# PCB.net
KiCad netlist of a schematic drawn in Altium Designer
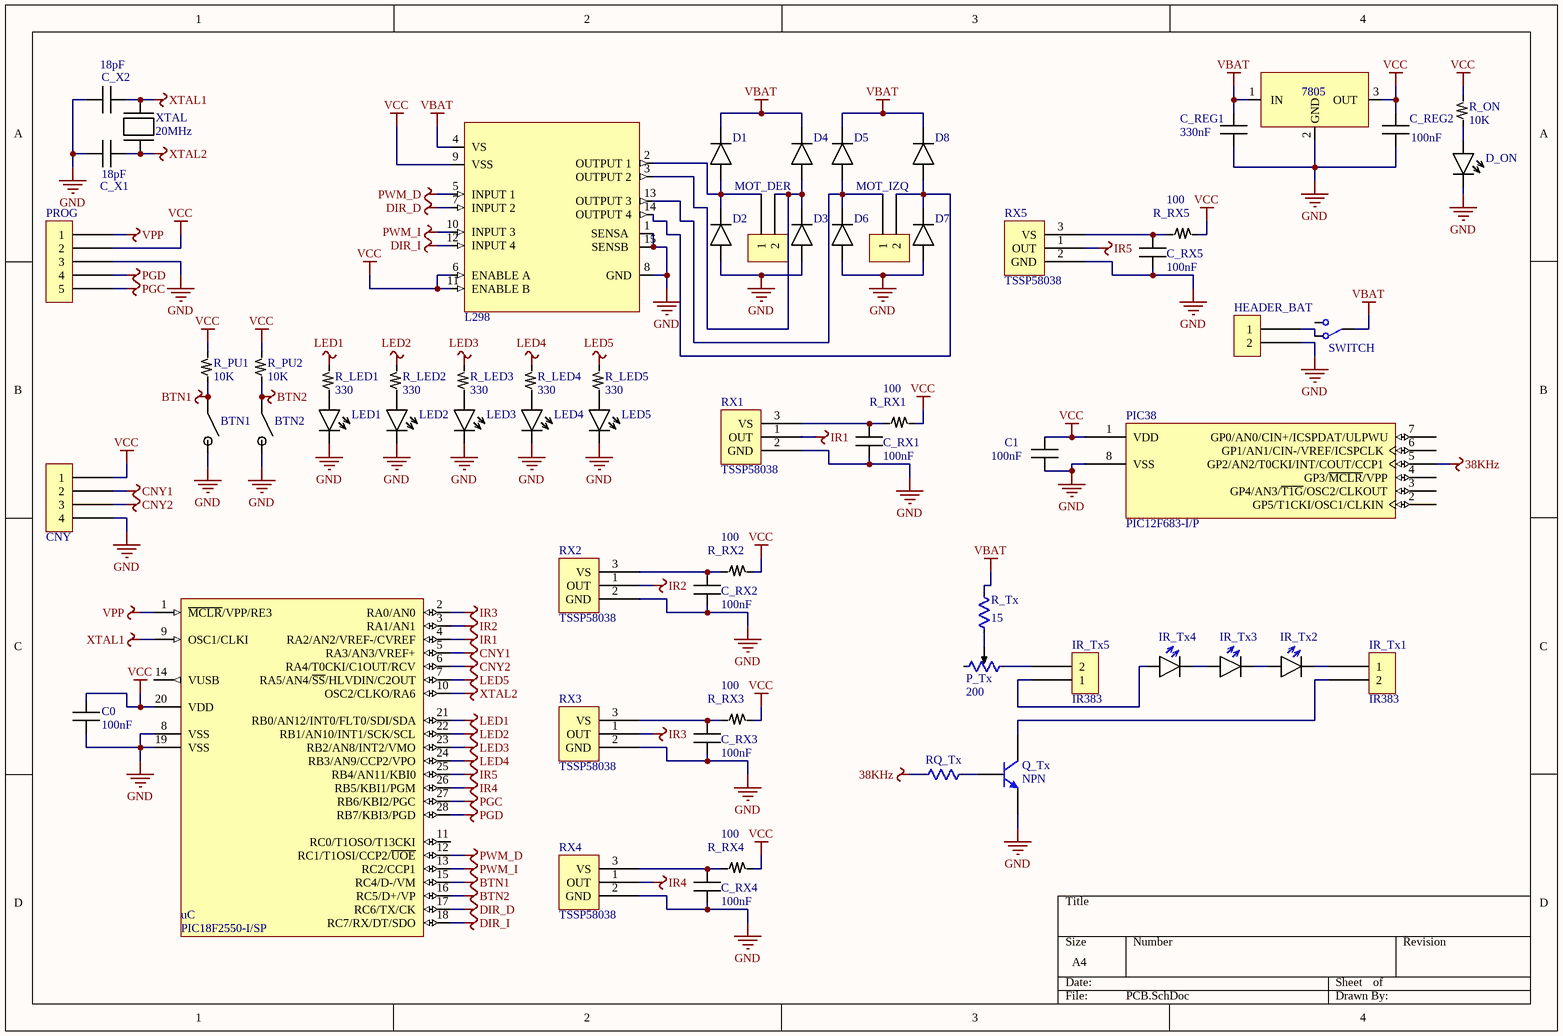
[diagram p0: PCB.SchDoc]

(export (version "E")
  (design (tool "Eeschema 10.0.6"))
  (components
    (comp (ref "7805") (value "LM7805") (footprint "TO-252") (libsource (lib "Components") (part "LM7805")))
    (comp (ref "BTN1")
      (value "SWITCH")
      (footprint "TACT_SWITCH-SMALL-4PIN")
      (libsource (lib "GlecerLib") (part "SWITCH"))
    )
    (comp (ref "BTN2")
      (value "SWITCH")
      (footprint "TACT_SWITCH-SMALL-4PIN")
      (libsource (lib "GlecerLib") (part "SWITCH"))
    )
    (comp (ref "C0")
      (value "100nF")
      (footprint "CAP-1206")
      (fields (field (name "Comment") "CAP-CER"))
      (libsource (lib "GlecerLib") (part "CAP-CER"))
    )
    (comp (ref "C1")
      (value "100nF")
      (footprint "CAP-1206")
      (fields (field (name "Comment") "CAP-CER"))
      (libsource (lib "GlecerLib") (part "CAP-CER"))
    )
    (comp (ref "CNY")
      (value "Header 1x4")
      (footprint "Header 1x4")
      (libsource (lib "AltiumLibrary") (part "Header 1x4"))
    )
    (comp (ref "C_REG1")
      (value "330nF")
      (footprint "CAP-1206")
      (fields (field (name "Comment") "CAP-CER"))
      (libsource (lib "GlecerLib") (part "CAP-CER"))
    )
    (comp (ref "C_REG2")
      (value "100nF")
      (footprint "CAP-1206")
      (fields (field (name "Comment") "CAP-CER"))
      (libsource (lib "GlecerLib") (part "CAP-CER"))
    )
    (comp (ref "C_RX1")
      (value "100nF")
      (footprint "CAP-1206")
      (fields (field (name "Comment") "CAP-CER"))
      (libsource (lib "GlecerLib") (part "CAP-CER"))
    )
    (comp (ref "C_RX2")
      (value "100nF")
      (footprint "CAP-1206")
      (fields (field (name "Comment") "CAP-CER"))
      (libsource (lib "GlecerLib") (part "CAP-CER"))
    )
    (comp (ref "C_RX3")
      (value "100nF")
      (footprint "CAP-1206")
      (fields (field (name "Comment") "CAP-CER"))
      (libsource (lib "GlecerLib") (part "CAP-CER"))
    )
    (comp (ref "C_RX4")
      (value "100nF")
      (footprint "CAP-1206")
      (fields (field (name "Comment") "CAP-CER"))
      (libsource (lib "GlecerLib") (part "CAP-CER"))
    )
    (comp (ref "C_RX5")
      (value "100nF")
      (footprint "CAP-1206")
      (fields (field (name "Comment") "CAP-CER"))
      (libsource (lib "GlecerLib") (part "CAP-CER"))
    )
    (comp (ref "C_X1")
      (value "18pF")
      (footprint "CAP-1206")
      (fields (field (name "Comment") "CAP-CER"))
      (libsource (lib "Components") (part "CAP-CER"))
    )
    (comp (ref "C_X2")
      (value "18pF")
      (footprint "CAP-1206")
      (fields (field (name "Comment") "CAP-CER"))
      (libsource (lib "Components") (part "CAP-CER"))
    )
    (comp (ref "D1") (value "~") (footprint "DO-214AC") (libsource (lib "GlecerLib") (part "DIODE")))
    (comp (ref "D2") (value "~") (footprint "DO-214AC") (libsource (lib "GlecerLib") (part "DIODE")))
    (comp (ref "D3") (value "~") (footprint "DO-214AC") (libsource (lib "GlecerLib") (part "DIODE")))
    (comp (ref "D4") (value "~") (footprint "DO-214AC") (libsource (lib "GlecerLib") (part "DIODE")))
    (comp (ref "D5") (value "~") (footprint "DO-214AC") (libsource (lib "GlecerLib") (part "DIODE")))
    (comp (ref "D6") (value "~") (footprint "DO-214AC") (libsource (lib "GlecerLib") (part "DIODE")))
    (comp (ref "D7") (value "~") (footprint "DO-214AC") (libsource (lib "GlecerLib") (part "DIODE")))
    (comp (ref "D8") (value "~") (footprint "DO-214AC") (libsource (lib "GlecerLib") (part "DIODE")))
    (comp (ref "D_ON") (value "LED") (footprint "LED-3MM-RED") (libsource (lib "Components") (part "LED")))
    (comp (ref "HEADER_BAT") (value "~") (footprint "HEADER 1x2") (libsource (lib "") (part "Header 1x2_1")))
    (comp (ref "IR_Tx1") (value "IR383") (footprint "HEADER 1x2") (libsource (lib "") (part "Header 1x2_2")))
    (comp (ref "IR_Tx2")
      (value "LED")
      (footprint "LED-3MM-YELLOW")
      (libsource (lib "AltiumLibrary") (part "LED"))
    )
    (comp (ref "IR_Tx3")
      (value "LED")
      (footprint "LED-3MM-YELLOW")
      (libsource (lib "AltiumLibrary") (part "LED"))
    )
    (comp (ref "IR_Tx4")
      (value "LED")
      (footprint "LED-3MM-YELLOW")
      (libsource (lib "AltiumLibrary") (part "LED"))
    )
    (comp (ref "IR_Tx5") (value "IR383") (footprint "HEADER 1x2") (libsource (lib "") (part "Header 1x2_3")))
    (comp (ref "L298") (value "L298") (footprint "Multiwatt15") (libsource (lib "Components") (part "L298")))
    (comp (ref "LED1") (value "LED") (footprint "LED-3MM-RED") (libsource (lib "Components") (part "LED")))
    (comp (ref "LED2") (value "LED") (footprint "LED-3MM-RED") (libsource (lib "Components") (part "LED")))
    (comp (ref "LED3") (value "LED") (footprint "LED-3MM-RED") (libsource (lib "Components") (part "LED")))
    (comp (ref "LED4") (value "LED") (footprint "LED-3MM-RED") (libsource (lib "Components") (part "LED")))
    (comp (ref "LED5") (value "LED") (footprint "LED-3MM-RED") (libsource (lib "Components") (part "LED")))
    (comp (ref "MOT_DER")
      (value "~")
      (footprint "HEADER 1x2")
      (libsource (lib "AltiumLibrary") (part "Header 1x2"))
    )
    (comp (ref "MOT_IZQ")
      (value "~")
      (footprint "HEADER 1x2")
      (libsource (lib "AltiumLibrary") (part "Header 1x2"))
    )
    (comp (ref "PIC38")
      (value "PIC12F683-I/P")
      (footprint "PDIP300-P8")
      (fields (field (name "PUBLISHER") "Altium Limited"))
      (libsource (lib "Microchip Microcontroller 8-Bit PIC12") (part "PIC12F683-I/P"))
    )
    (comp (ref "PROG")
      (value "~")
      (footprint "Header 1x5")
      (libsource (lib "AltiumLibrary") (part "Header 1x5"))
    )
    (comp (ref "P_Tx")
      (value "200")
      (footprint "POT-10TURN")
      (fields (field (name "Comment") "POT"))
      (libsource (lib "AltiumLibrary") (part "POT"))
    )
    (comp (ref "Q_Tx") (value "NPN") (footprint "SOT-23") (libsource (lib "AltiumLibrary") (part "NPN")))
    (comp (ref "RQ_Tx") (value "RES") (footprint "RES-1206") (libsource (lib "") (part "RES_1")))
    (comp (ref "RX1")
      (value "TSSP58038")
      (footprint "TSSP58038")
      (libsource (lib "GlecerLib") (part "TSSP58038"))
    )
    (comp (ref "RX2")
      (value "TSSP58038")
      (footprint "TSSP58038")
      (libsource (lib "GlecerLib") (part "TSSP58038"))
    )
    (comp (ref "RX3")
      (value "TSSP58038")
      (footprint "TSSP58038")
      (libsource (lib "GlecerLib") (part "TSSP58038"))
    )
    (comp (ref "RX4")
      (value "TSSP58038")
      (footprint "TSSP58038")
      (libsource (lib "GlecerLib") (part "TSSP58038"))
    )
    (comp (ref "RX5")
      (value "TSSP58038")
      (footprint "TSSP58038")
      (libsource (lib "GlecerLib") (part "TSSP58038"))
    )
    (comp (ref "R_LED1")
      (value "330")
      (footprint "RES-1206")
      (fields (field (name "Comment") "RES"))
      (libsource (lib "GlecerLib") (part "RES"))
    )
    (comp (ref "R_LED2")
      (value "330")
      (footprint "RES-1206")
      (fields (field (name "Comment") "RES"))
      (libsource (lib "GlecerLib") (part "RES"))
    )
    (comp (ref "R_LED3")
      (value "330")
      (footprint "RES-1206")
      (fields (field (name "Comment") "RES"))
      (libsource (lib "GlecerLib") (part "RES"))
    )
    (comp (ref "R_LED4")
      (value "330")
      (footprint "RES-1206")
      (fields (field (name "Comment") "RES"))
      (libsource (lib "GlecerLib") (part "RES"))
    )
    (comp (ref "R_LED5")
      (value "330")
      (footprint "RES-1206")
      (fields (field (name "Comment") "RES"))
      (libsource (lib "GlecerLib") (part "RES"))
    )
    (comp (ref "R_ON")
      (value "10K")
      (footprint "RES-1206")
      (fields (field (name "Comment") "RES"))
      (libsource (lib "GlecerLib") (part "RES"))
    )
    (comp (ref "R_PU1")
      (value "10K")
      (footprint "RES-1206")
      (fields (field (name "Comment") "RES"))
      (libsource (lib "GlecerLib") (part "RES"))
    )
    (comp (ref "R_PU2")
      (value "10K")
      (footprint "RES-1206")
      (fields (field (name "Comment") "RES"))
      (libsource (lib "GlecerLib") (part "RES"))
    )
    (comp (ref "R_RX1")
      (value "100")
      (footprint "RES-1206")
      (fields (field (name "Comment") "RES"))
      (libsource (lib "GlecerLib") (part "RES"))
    )
    (comp (ref "R_RX2")
      (value "100")
      (footprint "RES-1206")
      (fields (field (name "Comment") "RES"))
      (libsource (lib "GlecerLib") (part "RES"))
    )
    (comp (ref "R_RX3")
      (value "100")
      (footprint "RES-1206")
      (fields (field (name "Comment") "RES"))
      (libsource (lib "GlecerLib") (part "RES"))
    )
    (comp (ref "R_RX4")
      (value "100")
      (footprint "RES-1206")
      (fields (field (name "Comment") "RES"))
      (libsource (lib "GlecerLib") (part "RES"))
    )
    (comp (ref "R_RX5")
      (value "100")
      (footprint "RES-1206")
      (fields (field (name "Comment") "RES"))
      (libsource (lib "GlecerLib") (part "RES"))
    )
    (comp (ref "R_Tx")
      (value "15")
      (footprint "RES-1206")
      (fields (field (name "Comment") "RES"))
      (libsource (lib "AltiumLibrary") (part "RES"))
    )
    (comp (ref "SWITCH")
      (value "SLIDE-SWITCH")
      (footprint "SWITCH")
      (libsource (lib "AltiumLibrary") (part "SLIDE-SWITCH"))
    )
    (comp (ref "uC")
      (value "PIC18F2550-I/SP")
      (footprint "SPDIP300-SP28")
      (fields (field (name "PUBLISHER") "Altium Limited"))
      (libsource (lib "Microchip Microcontroller 8-Bit PIC18") (part "PIC18F2550-I/SP"))
    )
    (comp (ref "XTAL")
      (value "CRYSTAL-OSC")
      (footprint "HC-49/S")
      (fields (field (name "FREQUENCY") "20MHz"))
      (libsource (lib "Components") (part "CRYSTAL-OSC"))
    )
  )
  (nets
    (net (code "1") (name "38KHz") (class "Default")
      (node (ref "PIC38") (pin "5") (pinfunction "GP2/AN2/T0CKI/INT/COUT/CCP1_5") (pintype "bidirectional"))
      (node (ref "RQ_Tx") (pin "1") (pintype "passive"))
    )
    (net (code "2") (name "BTN1") (class "Default")
      (node (ref "BTN1") (pin "1") (pintype "passive"))
      (node (ref "R_PU1") (pin "2") (pintype "passive"))
      (node (ref "uC") (pin "15") (pinfunction "RC4/D-/VM_15") (pintype "bidirectional"))
    )
    (net (code "3") (name "BTN2") (class "Default")
      (node (ref "BTN2") (pin "1") (pintype "passive"))
      (node (ref "R_PU2") (pin "2") (pintype "passive"))
      (node (ref "uC") (pin "16") (pinfunction "RC5/D+/VP_16") (pintype "bidirectional"))
    )
    (net (code "4") (name "CNY1") (class "Default")
      (node (ref "CNY") (pin "2") (pinfunction "2_2") (pintype "passive"))
      (node (ref "uC") (pin "5") (pinfunction "RA3/AN3/VREF+_5") (pintype "bidirectional"))
    )
    (net (code "5") (name "CNY2") (class "Default")
      (node (ref "CNY") (pin "3") (pinfunction "3_3") (pintype "passive"))
      (node (ref "uC") (pin "6") (pinfunction "RA4/T0CKI/C1OUT/RCV_6") (pintype "bidirectional"))
    )
    (net (code "6") (name "DIR_D") (class "Default")
      (node (ref "L298") (pin "7") (pinfunction "INPUT_2_7") (pintype "input"))
      (node (ref "uC") (pin "17") (pinfunction "RC6/TX/CK_17") (pintype "bidirectional"))
    )
    (net (code "7") (name "DIR_I") (class "Default")
      (node (ref "L298") (pin "12") (pinfunction "INPUT_4_12") (pintype "input"))
      (node (ref "uC") (pin "18") (pinfunction "RC7/RX/DT/SDO_18") (pintype "bidirectional"))
    )
    (net (code "8") (name "GND") (class "Default")
      (node (ref "7805") (pin "2") (pinfunction "GND_2") (pintype "power_in"))
      (node (ref "BTN1") (pin "2") (pintype "passive"))
      (node (ref "BTN2") (pin "2") (pintype "passive"))
      (node (ref "C0") (pin "1") (pintype "passive"))
      (node (ref "C1") (pin "1") (pintype "passive"))
      (node (ref "CNY") (pin "4") (pinfunction "4_4") (pintype "passive"))
      (node (ref "C_REG1") (pin "1") (pintype "passive"))
      (node (ref "C_REG2") (pin "1") (pintype "passive"))
      (node (ref "C_RX1") (pin "2") (pintype "passive"))
      (node (ref "C_RX2") (pin "2") (pintype "passive"))
      (node (ref "C_RX3") (pin "2") (pintype "passive"))
      (node (ref "C_RX4") (pin "2") (pintype "passive"))
      (node (ref "C_RX5") (pin "2") (pintype "passive"))
      (node (ref "C_X1") (pin "1") (pintype "passive"))
      (node (ref "C_X2") (pin "1") (pintype "passive"))
      (node (ref "D2") (pin "A") (pintype "passive"))
      (node (ref "D3") (pin "A") (pintype "passive"))
      (node (ref "D6") (pin "A") (pintype "passive"))
      (node (ref "D7") (pin "A") (pintype "passive"))
      (node (ref "D_ON") (pin "K") (pintype "passive"))
      (node (ref "HEADER_BAT") (pin "2") (pinfunction "2_2") (pintype "passive"))
      (node (ref "L298") (pin "1") (pinfunction "SENSA_1") (pintype "power_in"))
      (node (ref "L298") (pin "15") (pinfunction "SENSB_15") (pintype "power_in"))
      (node (ref "L298") (pin "8") (pinfunction "GND_8") (pintype "power_in"))
      (node (ref "LED1") (pin "K") (pintype "passive"))
      (node (ref "LED2") (pin "K") (pintype "passive"))
      (node (ref "LED3") (pin "K") (pintype "passive"))
      (node (ref "LED4") (pin "K") (pintype "passive"))
      (node (ref "LED5") (pin "K") (pintype "passive"))
      (node (ref "PIC38") (pin "8") (pinfunction "VSS_8") (pintype "power_in"))
      (node (ref "PROG") (pin "3") (pinfunction "3_3") (pintype "passive"))
      (node (ref "Q_Tx") (pin "E") (pinfunction "E_E") (pintype "passive"))
      (node (ref "RX1") (pin "2") (pinfunction "GND_2") (pintype "power_in"))
      (node (ref "RX2") (pin "2") (pinfunction "GND_2") (pintype "power_in"))
      (node (ref "RX3") (pin "2") (pinfunction "GND_2") (pintype "power_in"))
      (node (ref "RX4") (pin "2") (pinfunction "GND_2") (pintype "power_in"))
      (node (ref "RX5") (pin "2") (pinfunction "GND_2") (pintype "power_in"))
      (node (ref "uC") (pin "19") (pinfunction "VSS_19") (pintype "power_in"))
      (node (ref "uC") (pin "8") (pinfunction "VSS_8") (pintype "power_in"))
    )
    (net (code "9") (name "IR1") (class "Default")
      (node (ref "RX1") (pin "1") (pinfunction "OUT_1") (pintype "power_in"))
      (node (ref "uC") (pin "4") (pinfunction "RA2/AN2/VREF-/CVREF_4") (pintype "bidirectional"))
    )
    (net (code "10") (name "IR2") (class "Default")
      (node (ref "RX2") (pin "1") (pinfunction "OUT_1") (pintype "power_in"))
      (node (ref "uC") (pin "3") (pinfunction "RA1/AN1_3") (pintype "bidirectional"))
    )
    (net (code "11") (name "IR3") (class "Default")
      (node (ref "RX3") (pin "1") (pinfunction "OUT_1") (pintype "power_in"))
      (node (ref "uC") (pin "2") (pinfunction "RA0/AN0_2") (pintype "bidirectional"))
    )
    (net (code "12") (name "IR4") (class "Default")
      (node (ref "RX4") (pin "1") (pinfunction "OUT_1") (pintype "power_in"))
      (node (ref "uC") (pin "26") (pinfunction "RB5/KBI1/PGM_26") (pintype "bidirectional"))
    )
    (net (code "13") (name "IR5") (class "Default")
      (node (ref "RX5") (pin "1") (pinfunction "OUT_1") (pintype "power_in"))
      (node (ref "uC") (pin "25") (pinfunction "RB4/AN11/KBI0_25") (pintype "bidirectional"))
    )
    (net (code "14") (name "LED1") (class "Default")
      (node (ref "R_LED1") (pin "1") (pintype "passive"))
      (node (ref "uC") (pin "21") (pinfunction "RB0/AN12/INT0/FLT0/SDI/SDA_21") (pintype "bidirectional"))
    )
    (net (code "15") (name "LED2") (class "Default")
      (node (ref "R_LED2") (pin "1") (pintype "passive"))
      (node (ref "uC") (pin "22") (pinfunction "RB1/AN10/INT1/SCK/SCL_22") (pintype "bidirectional"))
    )
    (net (code "16") (name "LED3") (class "Default")
      (node (ref "R_LED3") (pin "1") (pintype "passive"))
      (node (ref "uC") (pin "23") (pinfunction "RB2/AN8/INT2/VMO_23") (pintype "bidirectional"))
    )
    (net (code "17") (name "LED4") (class "Default")
      (node (ref "R_LED4") (pin "1") (pintype "passive"))
      (node (ref "uC") (pin "24") (pinfunction "RB3/AN9/CCP2/VPO_24") (pintype "bidirectional"))
    )
    (net (code "18") (name "LED5") (class "Default")
      (node (ref "R_LED5") (pin "1") (pintype "passive"))
      (node (ref "uC") (pin "7") (pinfunction "RA5/AN4/~{SS}/HLVDIN/C2OUT_7") (pintype "bidirectional"))
    )
    (net (code "19") (name "Net-(D_ON-PadA)") (class "Default")
      (node (ref "D_ON") (pin "A") (pintype "passive"))
      (node (ref "R_ON") (pin "2") (pintype "passive"))
    )
    (net (code "20") (name "Net-(HEADER_BAT-Pad1)") (class "Default")
      (node (ref "HEADER_BAT") (pin "1") (pinfunction "1_1") (pintype "passive"))
      (node (ref "SWITCH") (pin "1") (pintype "power_in"))
    )
    (net (code "21") (name "Net-(IR_Tx1-Pad1)") (class "Default")
      (node (ref "IR_Tx1") (pin "1") (pinfunction "1_1") (pintype "passive"))
      (node (ref "IR_Tx2") (pin "K") (pintype "passive"))
    )
    (net (code "22") (name "Net-(IR_Tx1-Pad2)") (class "Default")
      (node (ref "IR_Tx1") (pin "2") (pinfunction "2_2") (pintype "passive"))
      (node (ref "Q_Tx") (pin "C") (pinfunction "C_C") (pintype "passive"))
    )
    (net (code "23") (name "Net-(IR_Tx2-PadA)") (class "Default")
      (node (ref "IR_Tx2") (pin "A") (pintype "passive"))
      (node (ref "IR_Tx3") (pin "K") (pintype "passive"))
    )
    (net (code "24") (name "Net-(IR_Tx3-PadA)") (class "Default")
      (node (ref "IR_Tx3") (pin "A") (pintype "passive"))
      (node (ref "IR_Tx4") (pin "K") (pintype "passive"))
    )
    (net (code "25") (name "Net-(IR_Tx4-PadA)") (class "Default")
      (node (ref "IR_Tx4") (pin "A") (pintype "passive"))
      (node (ref "IR_Tx5") (pin "1") (pinfunction "1_1") (pintype "passive"))
    )
    (net (code "26") (name "Net-(IR_Tx5-Pad2)") (class "Default")
      (node (ref "IR_Tx5") (pin "2") (pinfunction "2_2") (pintype "passive"))
      (node (ref "P_Tx") (pin "3") (pintype "passive"))
    )
    (net (code "27") (name "Net-(L298-OUTPUT_1)") (class "Default")
      (node (ref "D1") (pin "A") (pintype "passive"))
      (node (ref "D2") (pin "K") (pintype "passive"))
      (node (ref "L298") (pin "2") (pinfunction "OUTPUT_1_2") (pintype "output"))
      (node (ref "MOT_DER") (pin "1") (pinfunction "1_1") (pintype "passive"))
    )
    (net (code "28") (name "Net-(L298-OUTPUT_2)") (class "Default")
      (node (ref "D3") (pin "K") (pintype "passive"))
      (node (ref "D4") (pin "A") (pintype "passive"))
      (node (ref "L298") (pin "3") (pinfunction "OUTPUT_2_3") (pintype "output"))
      (node (ref "MOT_DER") (pin "2") (pinfunction "2_2") (pintype "passive"))
    )
    (net (code "29") (name "Net-(L298-OUTPUT_3)") (class "Default")
      (node (ref "D5") (pin "A") (pintype "passive"))
      (node (ref "D6") (pin "K") (pintype "passive"))
      (node (ref "L298") (pin "13") (pinfunction "OUTPUT_3_13") (pintype "output"))
      (node (ref "MOT_IZQ") (pin "1") (pinfunction "1_1") (pintype "passive"))
    )
    (net (code "30") (name "Net-(L298-OUTPUT_4)") (class "Default")
      (node (ref "D7") (pin "K") (pintype "passive"))
      (node (ref "D8") (pin "A") (pintype "passive"))
      (node (ref "L298") (pin "14") (pinfunction "OUTPUT_4_14") (pintype "output"))
      (node (ref "MOT_IZQ") (pin "2") (pinfunction "2_2") (pintype "passive"))
    )
    (net (code "31") (name "Net-(LED1-PadA)") (class "Default")
      (node (ref "LED1") (pin "A") (pintype "passive"))
      (node (ref "R_LED1") (pin "2") (pintype "passive"))
    )
    (net (code "32") (name "Net-(LED2-PadA)") (class "Default")
      (node (ref "LED2") (pin "A") (pintype "passive"))
      (node (ref "R_LED2") (pin "2") (pintype "passive"))
    )
    (net (code "33") (name "Net-(LED3-PadA)") (class "Default")
      (node (ref "LED3") (pin "A") (pintype "passive"))
      (node (ref "R_LED3") (pin "2") (pintype "passive"))
    )
    (net (code "34") (name "Net-(LED4-PadA)") (class "Default")
      (node (ref "LED4") (pin "A") (pintype "passive"))
      (node (ref "R_LED4") (pin "2") (pintype "passive"))
    )
    (net (code "35") (name "Net-(LED5-PadA)") (class "Default")
      (node (ref "LED5") (pin "A") (pintype "passive"))
      (node (ref "R_LED5") (pin "2") (pintype "passive"))
    )
    (net (code "36") (name "Net-(P_Tx-Pad2)") (class "Default")
      (node (ref "P_Tx") (pin "2") (pintype "passive"))
      (node (ref "R_Tx") (pin "1") (pintype "passive"))
    )
    (net (code "37") (name "Net-(Q_Tx-PadB)") (class "Default")
      (node (ref "Q_Tx") (pin "B") (pinfunction "B_B") (pintype "passive"))
      (node (ref "RQ_Tx") (pin "2") (pintype "passive"))
    )
    (net (code "38") (name "Net-(RX1-VS)") (class "Default")
      (node (ref "C_RX1") (pin "1") (pintype "passive"))
      (node (ref "RX1") (pin "3") (pinfunction "VS_3") (pintype "power_in"))
      (node (ref "R_RX1") (pin "2") (pintype "passive"))
    )
    (net (code "39") (name "Net-(RX2-VS)") (class "Default")
      (node (ref "C_RX2") (pin "1") (pintype "passive"))
      (node (ref "RX2") (pin "3") (pinfunction "VS_3") (pintype "power_in"))
      (node (ref "R_RX2") (pin "2") (pintype "passive"))
    )
    (net (code "40") (name "Net-(RX3-VS)") (class "Default")
      (node (ref "C_RX3") (pin "1") (pintype "passive"))
      (node (ref "RX3") (pin "3") (pinfunction "VS_3") (pintype "power_in"))
      (node (ref "R_RX3") (pin "2") (pintype "passive"))
    )
    (net (code "41") (name "Net-(RX4-VS)") (class "Default")
      (node (ref "C_RX4") (pin "1") (pintype "passive"))
      (node (ref "RX4") (pin "3") (pinfunction "VS_3") (pintype "power_in"))
      (node (ref "R_RX4") (pin "2") (pintype "passive"))
    )
    (net (code "42") (name "Net-(RX5-VS)") (class "Default")
      (node (ref "C_RX5") (pin "1") (pintype "passive"))
      (node (ref "RX5") (pin "3") (pinfunction "VS_3") (pintype "power_in"))
      (node (ref "R_RX5") (pin "2") (pintype "passive"))
    )
    (net (code "43") (name "PGC") (class "Default")
      (node (ref "PROG") (pin "5") (pinfunction "5_5") (pintype "passive"))
      (node (ref "uC") (pin "27") (pinfunction "RB6/KBI2/PGC_27") (pintype "bidirectional"))
    )
    (net (code "44") (name "PGD") (class "Default")
      (node (ref "PROG") (pin "4") (pinfunction "4_4") (pintype "passive"))
      (node (ref "uC") (pin "28") (pinfunction "RB7/KBI3/PGD_28") (pintype "bidirectional"))
    )
    (net (code "45") (name "PWM_D") (class "Default")
      (node (ref "L298") (pin "5") (pinfunction "INPUT_1_5") (pintype "input"))
      (node (ref "uC") (pin "12") (pinfunction "RC1/T1OSI/CCP2/~{UOE}_12") (pintype "bidirectional"))
    )
    (net (code "46") (name "PWM_I") (class "Default")
      (node (ref "L298") (pin "10") (pinfunction "INPUT_3_10") (pintype "input"))
      (node (ref "uC") (pin "13") (pinfunction "RC2/CCP1_13") (pintype "bidirectional"))
    )
    (net (code "47") (name "VBAT") (class "Default")
      (node (ref "7805") (pin "1") (pinfunction "IN_1") (pintype "power_in"))
      (node (ref "C_REG1") (pin "2") (pintype "passive"))
      (node (ref "D1") (pin "K") (pintype "passive"))
      (node (ref "D4") (pin "K") (pintype "passive"))
      (node (ref "D5") (pin "K") (pintype "passive"))
      (node (ref "D8") (pin "K") (pintype "passive"))
      (node (ref "L298") (pin "4") (pinfunction "VS_4") (pintype "power_in"))
      (node (ref "R_Tx") (pin "2") (pintype "passive"))
      (node (ref "SWITCH") (pin "2") (pintype "power_in"))
    )
    (net (code "48") (name "VCC") (class "Default")
      (node (ref "7805") (pin "3") (pinfunction "OUT_3") (pintype "power_in"))
      (node (ref "C0") (pin "2") (pintype "passive"))
      (node (ref "C1") (pin "2") (pintype "passive"))
      (node (ref "CNY") (pin "1") (pinfunction "1_1") (pintype "passive"))
      (node (ref "C_REG2") (pin "2") (pintype "passive"))
      (node (ref "L298") (pin "11") (pinfunction "ENABLE_B_11") (pintype "input"))
      (node (ref "L298") (pin "6") (pinfunction "ENABLE_A_6") (pintype "input"))
      (node (ref "L298") (pin "9") (pinfunction "VSS_9") (pintype "power_in"))
      (node (ref "PIC38") (pin "1") (pinfunction "VDD_1") (pintype "power_in"))
      (node (ref "PROG") (pin "2") (pinfunction "2_2") (pintype "passive"))
      (node (ref "R_ON") (pin "1") (pintype "passive"))
      (node (ref "R_PU1") (pin "1") (pintype "passive"))
      (node (ref "R_PU2") (pin "1") (pintype "passive"))
      (node (ref "R_RX1") (pin "1") (pintype "passive"))
      (node (ref "R_RX2") (pin "1") (pintype "passive"))
      (node (ref "R_RX3") (pin "1") (pintype "passive"))
      (node (ref "R_RX4") (pin "1") (pintype "passive"))
      (node (ref "R_RX5") (pin "1") (pintype "passive"))
      (node (ref "uC") (pin "20") (pinfunction "VDD_20") (pintype "power_in"))
    )
    (net (code "49") (name "VPP") (class "Default")
      (node (ref "PROG") (pin "1") (pinfunction "1_1") (pintype "passive"))
      (node (ref "uC") (pin "1") (pinfunction "~{MCLR}/VPP/RE3_1") (pintype "input"))
    )
    (net (code "50") (name "XTAL1") (class "Default")
      (node (ref "C_X2") (pin "2") (pintype "passive"))
      (node (ref "XTAL") (pin "2") (pintype "passive"))
      (node (ref "uC") (pin "9") (pinfunction "OSC1/CLKI_9") (pintype "input"))
    )
    (net (code "51") (name "XTAL2") (class "Default")
      (node (ref "C_X1") (pin "2") (pintype "passive"))
      (node (ref "XTAL") (pin "1") (pintype "passive"))
      (node (ref "uC") (pin "10") (pinfunction "OSC2/CLKO/RA6_10") (pintype "bidirectional"))
    )
    (net (code "52") (name "unconnected-(PIC38-GP0{slash}AN0{slash}CIN+{slash}ICSPDAT{slash}ULPWU-Pad7)") (class "Default")
      (node (ref "PIC38") (pin "7") (pinfunction "GP0/AN0/CIN+/ICSPDAT/ULPWU_7") (pintype "bidirectional"))
    )
    (net (code "53") (name "unconnected-(PIC38-GP1{slash}AN1{slash}CIN-{slash}VREF{slash}ICSPCLK-Pad6)") (class "Default")
      (node (ref "PIC38") (pin "6") (pinfunction "GP1/AN1/CIN-/VREF/ICSPCLK_6") (pintype "bidirectional"))
    )
    (net (code "54") (name "unconnected-(PIC38-GP3{slash}~{MCLR}{slash}VPP-Pad4)") (class "Default")
      (node (ref "PIC38") (pin "4") (pinfunction "GP3/~{MCLR}/VPP_4") (pintype "bidirectional"))
    )
    (net (code "55") (name "unconnected-(PIC38-GP4{slash}AN3{slash}~{T1G}{slash}OSC2{slash}CLKOUT-Pad3)") (class "Default")
      (node (ref "PIC38") (pin "3") (pinfunction "GP4/AN3/~{T1G}/OSC2/CLKOUT_3") (pintype "bidirectional"))
    )
    (net (code "56") (name "unconnected-(PIC38-GP5{slash}T1CKI{slash}OSC1{slash}CLKIN-Pad2)") (class "Default")
      (node (ref "PIC38") (pin "2") (pinfunction "GP5/T1CKI/OSC1/CLKIN_2") (pintype "bidirectional"))
    )
    (net (code "57") (name "unconnected-(P_Tx-Pad1)") (class "Default")
      (node (ref "P_Tx") (pin "1") (pintype "passive"))
    )
    (net (code "58") (name "unconnected-(SWITCH-Pad3)") (class "Default")
      (node (ref "SWITCH") (pin "3") (pintype "power_in"))
    )
    (net (code "59") (name "unconnected-(uC-RC0{slash}T1OSO{slash}T13CKI-Pad11)") (class "Default")
      (node (ref "uC") (pin "11") (pinfunction "RC0/T1OSO/T13CKI_11") (pintype "bidirectional"))
    )
    (net (code "60") (name "unconnected-(uC-VUSB-Pad14)") (class "Default")
      (node (ref "uC") (pin "14") (pinfunction "VUSB_14") (pintype "output"))
    )
  )
)
